# NJM13700_MCP4922_DCA.net
KiCad netlist of a schematic drawn in EAGLE
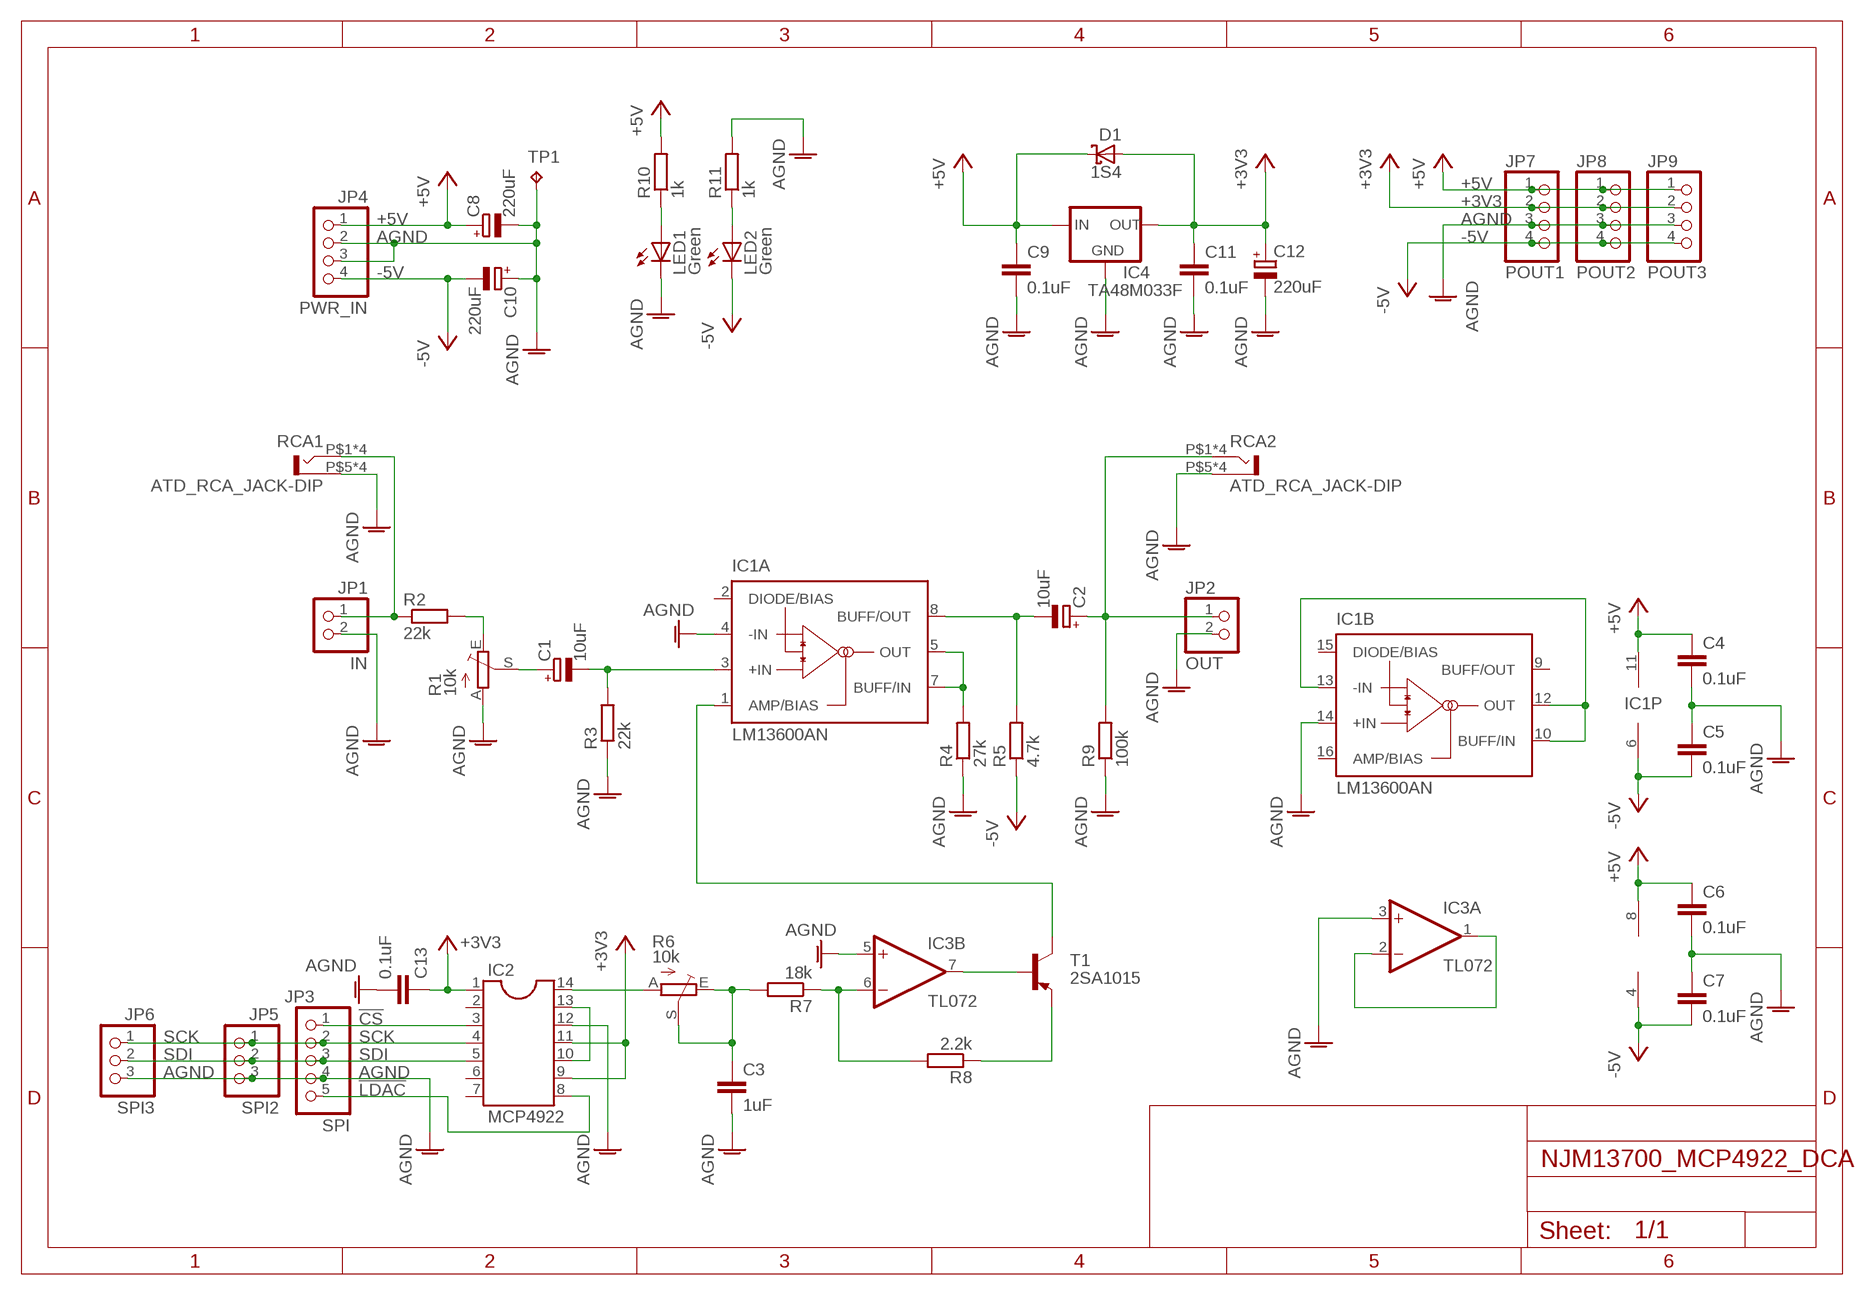
[diagram p0: schematic, sheet 1]

(export (version "E")
  (design (tool "Eeschema 10.0.6"))
  (components
    (comp (ref "C1")
      (value "10uF")
      (footprint "eagle-import:E5-6")
      (libsource (lib "eagle-import") (part "CPOL-EUE5-6"))
    )
    (comp (ref "C2")
      (value "10uF")
      (footprint "eagle-import:E2,5-6")
      (libsource (lib "eagle-import") (part "CPOL-EUE2.5-6"))
    )
    (comp (ref "C3")
      (value "1uF")
      (footprint "eagle-import:C050-024X044")
      (libsource (lib "eagle-import") (part "C-EU050-024X044"))
    )
    (comp (ref "C4")
      (value "0.1uF")
      (footprint "eagle-import:C025-024X044")
      (libsource (lib "eagle-import") (part "C-EU025-024X044"))
    )
    (comp (ref "C5")
      (value "0.1uF")
      (footprint "eagle-import:C025-024X044")
      (libsource (lib "eagle-import") (part "C-EU025-024X044"))
    )
    (comp (ref "C6")
      (value "0.1uF")
      (footprint "eagle-import:C025-024X044")
      (libsource (lib "eagle-import") (part "C-EU025-024X044"))
    )
    (comp (ref "C7")
      (value "0.1uF")
      (footprint "eagle-import:C025-024X044")
      (libsource (lib "eagle-import") (part "C-EU025-024X044"))
    )
    (comp (ref "C8")
      (value "220uF")
      (footprint "eagle-import:E5-8,5")
      (libsource (lib "eagle-import") (part "CPOL-EUE5-8.5"))
    )
    (comp (ref "C9")
      (value "0.1uF")
      (footprint "eagle-import:C025-024X044")
      (libsource (lib "eagle-import") (part "C-EU025-024X044"))
    )
    (comp (ref "C10")
      (value "220uF")
      (footprint "eagle-import:E5-8,5")
      (libsource (lib "eagle-import") (part "CPOL-EUE5-8.5"))
    )
    (comp (ref "C11")
      (value "0.1uF")
      (footprint "eagle-import:C025-024X044")
      (libsource (lib "eagle-import") (part "C-EU025-024X044"))
    )
    (comp (ref "C12")
      (value "220uF")
      (footprint "eagle-import:E5-8,5")
      (libsource (lib "eagle-import") (part "CPOL-EUE5-8.5"))
    )
    (comp (ref "C13")
      (value "0.1uF")
      (footprint "eagle-import:C025-024X044")
      (libsource (lib "eagle-import") (part "C-EU025-024X044"))
    )
    (comp (ref "D1")
      (value "1S4")
      (footprint "eagle-import:DO35-7")
      (libsource (lib "eagle-import") (part "SCHOTTKY-DIODEDO35-7"))
    )
    (comp (ref "IC1")
      (value "LM13600AN")
      (footprint "eagle-import:DIL16")
      (libsource (lib "eagle-import") (part "LM13600NA"))
    )
    (comp (ref "IC2")
      (value "MCP4922")
      (footprint "eagle-import:DIL14")
      (libsource (lib "eagle-import") (part "DIL14"))
    )
    (comp (ref "IC3")
      (value "TL072")
      (footprint "eagle-import:DIL08")
      (libsource (lib "eagle-import") (part "4558NLM"))
    )
    (comp (ref "IC4")
      (value "TA48M033F")
      (footprint "eagle-import:78XXS")
      (libsource (lib "eagle-import") (part "78XXS"))
    )
    (comp (ref "JP1")
      (value "IN")
      (footprint "eagle-import:1X02")
      (libsource (lib "eagle-import") (part "PINHD-1X2"))
    )
    (comp (ref "JP2")
      (value "OUT")
      (footprint "eagle-import:1X02")
      (libsource (lib "eagle-import") (part "PINHD-1X2"))
    )
    (comp (ref "JP3")
      (value "SPI")
      (footprint "eagle-import:1X05")
      (libsource (lib "eagle-import") (part "PINHD-1X5"))
    )
    (comp (ref "JP4")
      (value "PWR_IN")
      (footprint "eagle-import:1X04")
      (libsource (lib "eagle-import") (part "PINHD-1X4"))
    )
    (comp (ref "JP5")
      (value "SPI2")
      (footprint "eagle-import:1X03")
      (libsource (lib "eagle-import") (part "PINHD-1X3"))
    )
    (comp (ref "JP6")
      (value "SPI3")
      (footprint "eagle-import:1X03")
      (libsource (lib "eagle-import") (part "PINHD-1X3"))
    )
    (comp (ref "JP7")
      (value "POUT1")
      (footprint "eagle-import:1X04")
      (libsource (lib "eagle-import") (part "PINHD-1X4"))
    )
    (comp (ref "JP8")
      (value "POUT2")
      (footprint "eagle-import:1X04")
      (libsource (lib "eagle-import") (part "PINHD-1X4"))
    )
    (comp (ref "JP9")
      (value "POUT3")
      (footprint "eagle-import:1X04")
      (libsource (lib "eagle-import") (part "PINHD-1X4"))
    )
    (comp (ref "LED1")
      (value "Green")
      (footprint "eagle-import:LED3MM")
      (libsource (lib "eagle-import") (part "LED3MM"))
    )
    (comp (ref "LED2")
      (value "Green")
      (footprint "eagle-import:LED3MM")
      (libsource (lib "eagle-import") (part "LED3MM"))
    )
    (comp (ref "R1")
      (value "10k")
      (footprint "eagle-import:B25P")
      (libsource (lib "eagle-import") (part "TRIM_EU-B25P"))
    )
    (comp (ref "R2")
      (value "22k")
      (footprint "eagle-import:0207_7")
      (libsource (lib "eagle-import") (part "R-EU_0207/7"))
    )
    (comp (ref "R3")
      (value "22k")
      (footprint "eagle-import:0207_7")
      (libsource (lib "eagle-import") (part "R-EU_0207/7"))
    )
    (comp (ref "R4")
      (value "27k")
      (footprint "eagle-import:0207_7")
      (libsource (lib "eagle-import") (part "R-EU_0207/7"))
    )
    (comp (ref "R5")
      (value "4.7k")
      (footprint "eagle-import:0207_7")
      (libsource (lib "eagle-import") (part "R-EU_0207/7"))
    )
    (comp (ref "R6")
      (value "10k")
      (footprint "eagle-import:B25P")
      (libsource (lib "eagle-import") (part "TRIM_EU-B25P"))
    )
    (comp (ref "R7")
      (value "18k")
      (footprint "eagle-import:0207_7")
      (libsource (lib "eagle-import") (part "R-EU_0207/7"))
    )
    (comp (ref "R8")
      (value "2.2k")
      (footprint "eagle-import:0207_7")
      (libsource (lib "eagle-import") (part "R-EU_0207/7"))
    )
    (comp (ref "R9")
      (value "100k")
      (footprint "eagle-import:0207_7")
      (libsource (lib "eagle-import") (part "R-EU_0207/7"))
    )
    (comp (ref "R10")
      (value "1k")
      (footprint "eagle-import:0207_7")
      (libsource (lib "eagle-import") (part "R-EU_0207/7"))
    )
    (comp (ref "R11")
      (value "1k")
      (footprint "eagle-import:0207_7")
      (libsource (lib "eagle-import") (part "R-EU_0207/7"))
    )
    (comp (ref "RCA1")
      (value "ATD_RCA_JACK-DIP")
      (footprint "eagle-import:ATD_RCA_JACK_DIP")
      (libsource (lib "eagle-import") (part "ATD_RCA_JACK-DIP"))
    )
    (comp (ref "RCA2")
      (value "ATD_RCA_JACK-DIP")
      (footprint "eagle-import:ATD_RCA_JACK_DIP")
      (libsource (lib "eagle-import") (part "ATD_RCA_JACK-DIP"))
    )
    (comp (ref "T1")
      (value "2SA1015")
      (footprint "eagle-import:TO92-ECB")
      (libsource (lib "eagle-import") (part "-PNP-TO92-ECB"))
    )
    (comp (ref "TP1")
      (value "TPPAD1-13")
      (footprint "eagle-import:P1-13")
      (libsource (lib "eagle-import") (part "TPPAD1-13"))
    )
  )
  (nets
    (net (code "1") (name "+3V3") (class "Default")
      (node (ref "C11") (pin "1") (pinfunction "1_1") (pintype "passive"))
      (node (ref "C12") (pin "+") (pinfunction "+_+") (pintype "passive"))
      (node (ref "C13") (pin "2") (pinfunction "2_2") (pintype "passive"))
      (node (ref "D1") (pin "A") (pinfunction "A_A") (pintype "passive"))
      (node (ref "IC2") (pin "1") (pinfunction "1_1") (pintype "passive"))
      (node (ref "IC2") (pin "11") (pinfunction "11_11") (pintype "passive"))
      (node (ref "IC2") (pin "9") (pinfunction "9_9") (pintype "passive"))
      (node (ref "IC4") (pin "OUT") (pinfunction "OUT_OUT") (pintype "passive"))
      (node (ref "JP7") (pin "2") (pinfunction "2_2") (pintype "passive"))
      (node (ref "JP8") (pin "2") (pinfunction "2_2") (pintype "passive"))
      (node (ref "JP9") (pin "2") (pinfunction "2_2") (pintype "passive"))
    )
    (net (code "2") (name "+5V") (class "Default")
      (node (ref "C4") (pin "1") (pinfunction "1_1") (pintype "passive"))
      (node (ref "C6") (pin "1") (pinfunction "1_1") (pintype "passive"))
      (node (ref "C8") (pin "+") (pinfunction "+_+") (pintype "passive"))
      (node (ref "C9") (pin "1") (pinfunction "1_1") (pintype "passive"))
      (node (ref "D1") (pin "C") (pinfunction "C_C") (pintype "passive"))
      (node (ref "IC1") (pin "11") (pinfunction "V+_11") (pintype "power_in"))
      (node (ref "IC3") (pin "8") (pinfunction "V+_8") (pintype "power_in"))
      (node (ref "IC4") (pin "IN") (pinfunction "IN_IN") (pintype "input"))
      (node (ref "JP4") (pin "1") (pinfunction "1_1") (pintype "passive"))
      (node (ref "JP7") (pin "1") (pinfunction "1_1") (pintype "passive"))
      (node (ref "JP8") (pin "1") (pinfunction "1_1") (pintype "passive"))
      (node (ref "JP9") (pin "1") (pinfunction "1_1") (pintype "passive"))
      (node (ref "R10") (pin "2") (pinfunction "2_2") (pintype "passive"))
    )
    (net (code "3") (name "-5V") (class "Default")
      (node (ref "C10") (pin "-") (pinfunction "-_-") (pintype "passive"))
      (node (ref "C5") (pin "2") (pinfunction "2_2") (pintype "passive"))
      (node (ref "C7") (pin "2") (pinfunction "2_2") (pintype "passive"))
      (node (ref "IC1") (pin "6") (pinfunction "V-_6") (pintype "power_in"))
      (node (ref "IC3") (pin "4") (pinfunction "V-_4") (pintype "power_in"))
      (node (ref "JP4") (pin "4") (pinfunction "4_4") (pintype "passive"))
      (node (ref "JP7") (pin "4") (pinfunction "4_4") (pintype "passive"))
      (node (ref "JP8") (pin "4") (pinfunction "4_4") (pintype "passive"))
      (node (ref "JP9") (pin "4") (pinfunction "4_4") (pintype "passive"))
      (node (ref "LED2") (pin "K") (pinfunction "C_K") (pintype "passive"))
      (node (ref "R5") (pin "1") (pinfunction "1_1") (pintype "passive"))
    )
    (net (code "4") (name "/SCK") (class "Default")
      (node (ref "IC2") (pin "4") (pinfunction "4_4") (pintype "passive"))
      (node (ref "JP3") (pin "2") (pinfunction "2_2") (pintype "passive"))
      (node (ref "JP5") (pin "1") (pinfunction "1_1") (pintype "passive"))
      (node (ref "JP6") (pin "1") (pinfunction "1_1") (pintype "passive"))
    )
    (net (code "5") (name "/SDI") (class "Default")
      (node (ref "IC2") (pin "5") (pinfunction "5_5") (pintype "passive"))
      (node (ref "JP3") (pin "3") (pinfunction "3_3") (pintype "passive"))
      (node (ref "JP5") (pin "2") (pinfunction "2_2") (pintype "passive"))
      (node (ref "JP6") (pin "2") (pinfunction "2_2") (pintype "passive"))
    )
    (net (code "6") (name "/~{CS}") (class "Default")
      (node (ref "IC2") (pin "3") (pinfunction "3_3") (pintype "passive"))
      (node (ref "JP3") (pin "1") (pinfunction "1_1") (pintype "passive"))
    )
    (net (code "7") (name "/~{LDAC}") (class "Default")
      (node (ref "IC2") (pin "8") (pinfunction "8_8") (pintype "passive"))
      (node (ref "JP3") (pin "5") (pinfunction "5_5") (pintype "passive"))
    )
    (net (code "8") (name "AGND") (class "Default")
      (node (ref "C10") (pin "+") (pinfunction "+_+") (pintype "passive"))
      (node (ref "C11") (pin "2") (pinfunction "2_2") (pintype "passive"))
      (node (ref "C12") (pin "-") (pinfunction "-_-") (pintype "passive"))
      (node (ref "C13") (pin "1") (pinfunction "1_1") (pintype "passive"))
      (node (ref "C3") (pin "2") (pinfunction "2_2") (pintype "passive"))
      (node (ref "C4") (pin "2") (pinfunction "2_2") (pintype "passive"))
      (node (ref "C5") (pin "1") (pinfunction "1_1") (pintype "passive"))
      (node (ref "C6") (pin "2") (pinfunction "2_2") (pintype "passive"))
      (node (ref "C7") (pin "1") (pinfunction "1_1") (pintype "passive"))
      (node (ref "C8") (pin "-") (pinfunction "-_-") (pintype "passive"))
      (node (ref "C9") (pin "2") (pinfunction "2_2") (pintype "passive"))
      (node (ref "IC1") (pin "14") (pinfunction "+IN_14") (pintype "input"))
      (node (ref "IC1") (pin "4") (pinfunction "-IN_4") (pintype "input"))
      (node (ref "IC2") (pin "12") (pinfunction "12_12") (pintype "passive"))
      (node (ref "IC3") (pin "3") (pinfunction "+IN_3") (pintype "input"))
      (node (ref "IC3") (pin "5") (pinfunction "+IN_5") (pintype "input"))
      (node (ref "IC4") (pin "GND") (pinfunction "GND_GND") (pintype "input"))
      (node (ref "JP1") (pin "2") (pinfunction "2_2") (pintype "passive"))
      (node (ref "JP2") (pin "2") (pinfunction "2_2") (pintype "passive"))
      (node (ref "JP3") (pin "4") (pinfunction "4_4") (pintype "passive"))
      (node (ref "JP4") (pin "2") (pinfunction "2_2") (pintype "passive"))
      (node (ref "JP4") (pin "3") (pinfunction "3_3") (pintype "passive"))
      (node (ref "JP5") (pin "3") (pinfunction "3_3") (pintype "passive"))
      (node (ref "JP6") (pin "3") (pinfunction "3_3") (pintype "passive"))
      (node (ref "JP7") (pin "3") (pinfunction "3_3") (pintype "passive"))
      (node (ref "JP8") (pin "3") (pinfunction "3_3") (pintype "passive"))
      (node (ref "JP9") (pin "3") (pinfunction "3_3") (pintype "passive"))
      (node (ref "LED1") (pin "K") (pinfunction "C_K") (pintype "passive"))
      (node (ref "R1") (pin "A") (pinfunction "A_A") (pintype "passive"))
      (node (ref "R11") (pin "2") (pinfunction "2_2") (pintype "passive"))
      (node (ref "R3") (pin "1") (pinfunction "1_1") (pintype "passive"))
      (node (ref "R4") (pin "1") (pinfunction "1_1") (pintype "passive"))
      (node (ref "R9") (pin "1") (pinfunction "1_1") (pintype "passive"))
      (node (ref "RCA1") (pin "P$5") (pinfunction "S_P$5") (pintype "passive"))
      (node (ref "RCA1") (pin "P$6") (pinfunction "S_P$6") (pintype "passive"))
      (node (ref "RCA1") (pin "P$7") (pinfunction "S_P$7") (pintype "passive"))
      (node (ref "RCA1") (pin "P$8") (pinfunction "S_P$8") (pintype "passive"))
      (node (ref "RCA2") (pin "P$5") (pinfunction "S_P$5") (pintype "passive"))
      (node (ref "RCA2") (pin "P$6") (pinfunction "S_P$6") (pintype "passive"))
      (node (ref "RCA2") (pin "P$7") (pinfunction "S_P$7") (pintype "passive"))
      (node (ref "RCA2") (pin "P$8") (pinfunction "S_P$8") (pintype "passive"))
      (node (ref "TP1") (pin "TP") (pinfunction "TP_TP") (pintype "input"))
    )
    (net (code "9") (name "Net-(C1-Pad+)") (class "Default")
      (node (ref "C1") (pin "+") (pinfunction "+_+") (pintype "passive"))
      (node (ref "R1") (pin "S") (pinfunction "S_S") (pintype "passive"))
    )
    (net (code "10") (name "Net-(C2-Pad+)") (class "Default")
      (node (ref "C2") (pin "+") (pinfunction "+_+") (pintype "passive"))
      (node (ref "JP2") (pin "1") (pinfunction "1_1") (pintype "passive"))
      (node (ref "R9") (pin "2") (pinfunction "2_2") (pintype "passive"))
      (node (ref "RCA2") (pin "P$1") (pinfunction "T_P$1") (pintype "passive"))
      (node (ref "RCA2") (pin "P$2") (pinfunction "T_P$2") (pintype "passive"))
      (node (ref "RCA2") (pin "P$3") (pinfunction "T_P$3") (pintype "passive"))
      (node (ref "RCA2") (pin "P$4") (pinfunction "T_P$4") (pintype "passive"))
    )
    (net (code "11") (name "Net-(C3-Pad1)") (class "Default")
      (node (ref "C3") (pin "1") (pinfunction "1_1") (pintype "passive"))
      (node (ref "R6") (pin "E") (pinfunction "E_E") (pintype "passive"))
      (node (ref "R6") (pin "S") (pinfunction "S_S") (pintype "passive"))
      (node (ref "R7") (pin "2") (pinfunction "2_2") (pintype "passive"))
    )
    (net (code "12") (name "Net-(IC1A-+IN)") (class "Default")
      (node (ref "C1") (pin "-") (pinfunction "-_-") (pintype "passive"))
      (node (ref "IC1") (pin "3") (pinfunction "+IN_3") (pintype "input"))
      (node (ref "R3") (pin "2") (pinfunction "2_2") (pintype "passive"))
    )
    (net (code "13") (name "Net-(IC1A-AMP{slash}BIAS)") (class "Default")
      (node (ref "IC1") (pin "1") (pinfunction "AMP/BIAS_1") (pintype "passive"))
      (node (ref "T1") (pin "C") (pinfunction "C_C") (pintype "passive"))
    )
    (net (code "14") (name "Net-(IC1A-BUFF{slash}IN)") (class "Default")
      (node (ref "IC1") (pin "5") (pinfunction "OUT_5") (pintype "output"))
      (node (ref "IC1") (pin "7") (pinfunction "BUFF/IN_7") (pintype "input"))
      (node (ref "R4") (pin "2") (pinfunction "2_2") (pintype "passive"))
    )
    (net (code "15") (name "Net-(IC1A-BUFF{slash}OUT)") (class "Default")
      (node (ref "C2") (pin "-") (pinfunction "-_-") (pintype "passive"))
      (node (ref "IC1") (pin "8") (pinfunction "BUFF/OUT_8") (pintype "output"))
      (node (ref "R5") (pin "2") (pinfunction "2_2") (pintype "passive"))
    )
    (net (code "16") (name "Net-(IC1B--IN)") (class "Default")
      (node (ref "IC1") (pin "10") (pinfunction "BUFF/IN_10") (pintype "input"))
      (node (ref "IC1") (pin "12") (pinfunction "OUT_12") (pintype "output"))
      (node (ref "IC1") (pin "13") (pinfunction "-IN_13") (pintype "input"))
    )
    (net (code "17") (name "Net-(IC2-Pad10)") (class "Default")
      (node (ref "IC2") (pin "10") (pinfunction "10_10") (pintype "passive"))
      (node (ref "IC2") (pin "13") (pinfunction "13_13") (pintype "passive"))
    )
    (net (code "18") (name "Net-(IC2-Pad14)") (class "Default")
      (node (ref "IC2") (pin "14") (pinfunction "14_14") (pintype "passive"))
      (node (ref "R6") (pin "A") (pinfunction "A_A") (pintype "passive"))
    )
    (net (code "19") (name "Net-(IC3A--IN)") (class "Default")
      (node (ref "IC3") (pin "1") (pinfunction "OUT_1") (pintype "output"))
      (node (ref "IC3") (pin "2") (pinfunction "-IN_2") (pintype "input"))
    )
    (net (code "20") (name "Net-(IC3B--IN)") (class "Default")
      (node (ref "IC3") (pin "6") (pinfunction "-IN_6") (pintype "input"))
      (node (ref "R7") (pin "1") (pinfunction "1_1") (pintype "passive"))
      (node (ref "R8") (pin "2") (pinfunction "2_2") (pintype "passive"))
    )
    (net (code "21") (name "Net-(IC3B-OUT)") (class "Default")
      (node (ref "IC3") (pin "7") (pinfunction "OUT_7") (pintype "output"))
      (node (ref "T1") (pin "B") (pinfunction "B_B") (pintype "passive"))
    )
    (net (code "22") (name "Net-(JP1-Pad1)") (class "Default")
      (node (ref "JP1") (pin "1") (pinfunction "1_1") (pintype "passive"))
      (node (ref "R2") (pin "1") (pinfunction "1_1") (pintype "passive"))
      (node (ref "RCA1") (pin "P$1") (pinfunction "T_P$1") (pintype "passive"))
      (node (ref "RCA1") (pin "P$2") (pinfunction "T_P$2") (pintype "passive"))
      (node (ref "RCA1") (pin "P$3") (pinfunction "T_P$3") (pintype "passive"))
      (node (ref "RCA1") (pin "P$4") (pinfunction "T_P$4") (pintype "passive"))
    )
    (net (code "23") (name "Net-(LED1-PadA)") (class "Default")
      (node (ref "LED1") (pin "A") (pinfunction "A_A") (pintype "passive"))
      (node (ref "R10") (pin "1") (pinfunction "1_1") (pintype "passive"))
    )
    (net (code "24") (name "Net-(LED2-PadA)") (class "Default")
      (node (ref "LED2") (pin "A") (pinfunction "A_A") (pintype "passive"))
      (node (ref "R11") (pin "1") (pinfunction "1_1") (pintype "passive"))
    )
    (net (code "25") (name "Net-(R1-PadE)") (class "Default")
      (node (ref "R1") (pin "E") (pinfunction "E_E") (pintype "passive"))
      (node (ref "R2") (pin "2") (pinfunction "2_2") (pintype "passive"))
    )
    (net (code "26") (name "Net-(R8-Pad1)") (class "Default")
      (node (ref "R8") (pin "1") (pinfunction "1_1") (pintype "passive"))
      (node (ref "T1") (pin "E") (pinfunction "E_E") (pintype "passive"))
    )
    (net (code "27") (name "unconnected-(IC1A-DIODE{slash}BIAS-Pad2)") (class "Default")
      (node (ref "IC1") (pin "2") (pinfunction "DIODE/BIAS_2") (pintype "passive"))
    )
    (net (code "28") (name "unconnected-(IC1B-AMP{slash}BIAS-Pad16)") (class "Default")
      (node (ref "IC1") (pin "16") (pinfunction "AMP/BIAS_16") (pintype "passive"))
    )
    (net (code "29") (name "unconnected-(IC1B-BUFF{slash}OUT-Pad9)") (class "Default")
      (node (ref "IC1") (pin "9") (pinfunction "BUFF/OUT_9") (pintype "output"))
    )
    (net (code "30") (name "unconnected-(IC1B-DIODE{slash}BIAS-Pad15)") (class "Default")
      (node (ref "IC1") (pin "15") (pinfunction "DIODE/BIAS_15") (pintype "passive"))
    )
    (net (code "31") (name "unconnected-(IC2-Pad2)") (class "Default")
      (node (ref "IC2") (pin "2") (pinfunction "2_2") (pintype "passive"))
    )
    (net (code "32") (name "unconnected-(IC2-Pad6)") (class "Default")
      (node (ref "IC2") (pin "6") (pinfunction "6_6") (pintype "passive"))
    )
    (net (code "33") (name "unconnected-(IC2-Pad7)") (class "Default")
      (node (ref "IC2") (pin "7") (pinfunction "7_7") (pintype "passive"))
    )
  )
)
